# Package_Sockets.net
KiCad netlist of a schematic drawn in Altium Designer
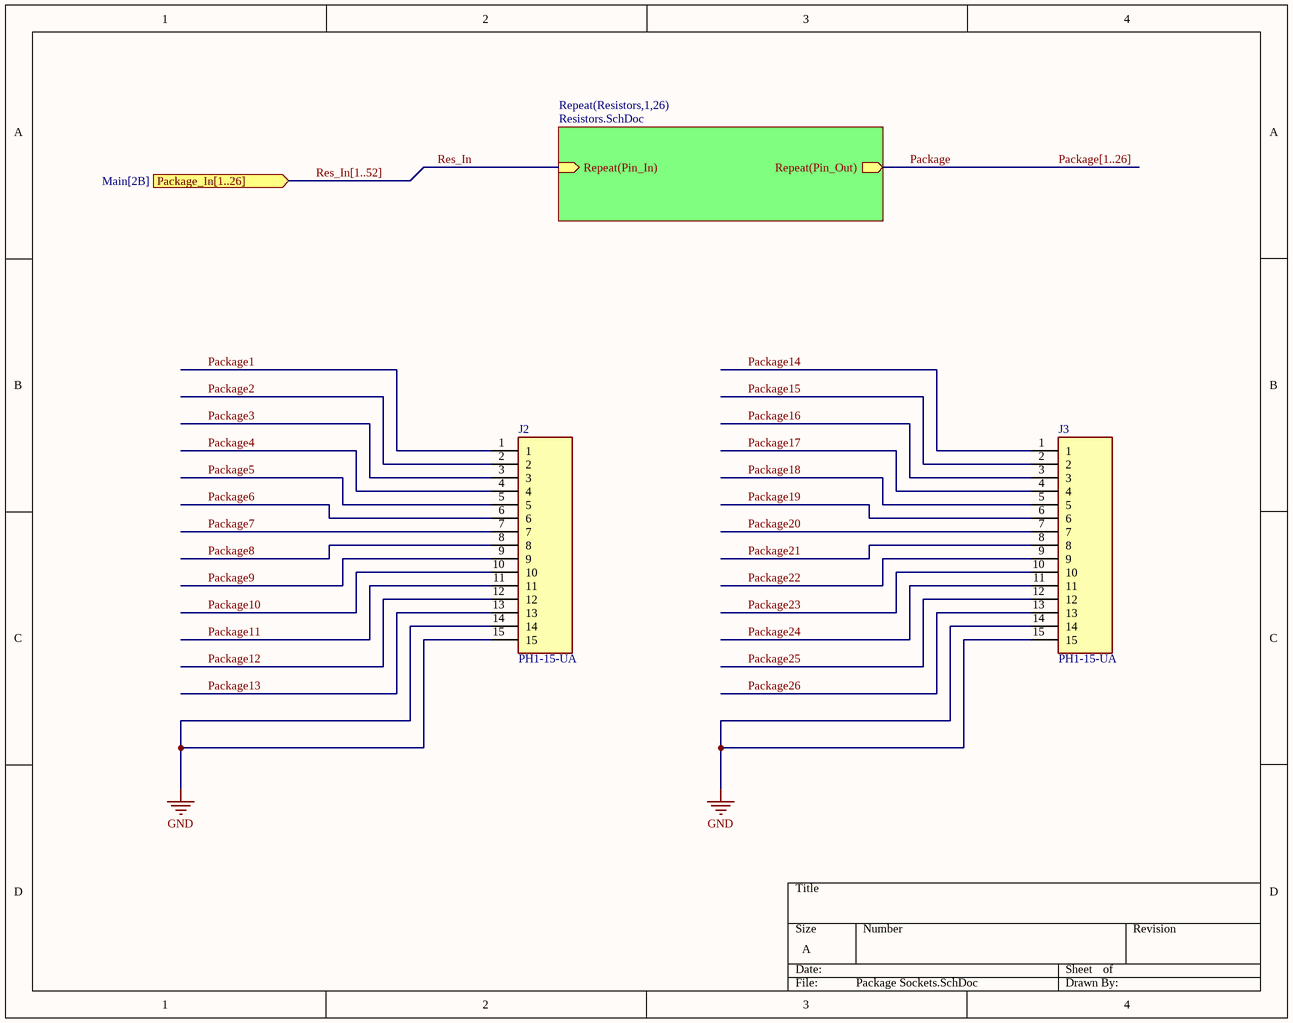
[diagram p0: Package Sockets.SchDoc]

(export (version "E")
  (design (tool "Eeschema 10.0.6"))
  (components
    (comp (ref "J2")
      (value "PH1-15-UA")
      (footprint "Packaging:HDRV15W64P0X254_1X15_3810X249X886P")
      (description "Connector")
      (fields (field (name "MOUSER PART NUMBER") "737-PH1-15-UA"))
      (libsource (lib "*") (part "PH1-15-UA"))
    )
    (comp (ref "J3")
      (value "PH1-15-UA")
      (footprint "Packaging:HDRV15W64P0X254_1X15_3810X249X886P")
      (description "Connector")
      (fields (field (name "MOUSER PART NUMBER") "737-PH1-15-UA"))
      (libsource (lib "*") (part "PH1-15-UA"))
    )
  )
  (nets
    (net (code "54") (name "/Package1") (class "Default")
      (node (ref "J2") (pin "1") (pinfunction "1_1") (pintype "passive"))
    )
    (net (code "55") (name "/Package2") (class "Default")
      (node (ref "J2") (pin "2") (pinfunction "2_2") (pintype "passive"))
    )
    (net (code "56") (name "/Package3") (class "Default")
      (node (ref "J2") (pin "3") (pinfunction "3_3") (pintype "passive"))
    )
    (net (code "57") (name "/Package4") (class "Default")
      (node (ref "J2") (pin "4") (pinfunction "4_4") (pintype "passive"))
    )
    (net (code "58") (name "/Package5") (class "Default")
      (node (ref "J2") (pin "5") (pinfunction "5_5") (pintype "passive"))
    )
    (net (code "59") (name "/Package6") (class "Default")
      (node (ref "J2") (pin "6") (pinfunction "6_6") (pintype "passive"))
    )
    (net (code "60") (name "/Package7") (class "Default")
      (node (ref "J2") (pin "7") (pinfunction "7_7") (pintype "passive"))
    )
    (net (code "61") (name "/Package8") (class "Default")
      (node (ref "J2") (pin "8") (pinfunction "8_8") (pintype "passive"))
    )
    (net (code "62") (name "/Package9") (class "Default")
      (node (ref "J2") (pin "9") (pinfunction "9_9") (pintype "passive"))
    )
    (net (code "63") (name "/Package10") (class "Default")
      (node (ref "J2") (pin "10") (pinfunction "10_10") (pintype "passive"))
    )
    (net (code "64") (name "/Package11") (class "Default")
      (node (ref "J2") (pin "11") (pinfunction "11_11") (pintype "passive"))
    )
    (net (code "65") (name "/Package12") (class "Default")
      (node (ref "J2") (pin "12") (pinfunction "12_12") (pintype "passive"))
    )
    (net (code "66") (name "/Package13") (class "Default")
      (node (ref "J2") (pin "13") (pinfunction "13_13") (pintype "passive"))
    )
    (net (code "67") (name "/Package14") (class "Default")
      (node (ref "J3") (pin "1") (pinfunction "1_1") (pintype "passive"))
    )
    (net (code "68") (name "/Package15") (class "Default")
      (node (ref "J3") (pin "2") (pinfunction "2_2") (pintype "passive"))
    )
    (net (code "69") (name "/Package16") (class "Default")
      (node (ref "J3") (pin "3") (pinfunction "3_3") (pintype "passive"))
    )
    (net (code "70") (name "/Package17") (class "Default")
      (node (ref "J3") (pin "4") (pinfunction "4_4") (pintype "passive"))
    )
    (net (code "71") (name "/Package18") (class "Default")
      (node (ref "J3") (pin "5") (pinfunction "5_5") (pintype "passive"))
    )
    (net (code "72") (name "/Package19") (class "Default")
      (node (ref "J3") (pin "6") (pinfunction "6_6") (pintype "passive"))
    )
    (net (code "73") (name "/Package20") (class "Default")
      (node (ref "J3") (pin "7") (pinfunction "7_7") (pintype "passive"))
    )
    (net (code "74") (name "/Package21") (class "Default")
      (node (ref "J3") (pin "8") (pinfunction "8_8") (pintype "passive"))
    )
    (net (code "75") (name "/Package22") (class "Default")
      (node (ref "J3") (pin "9") (pinfunction "9_9") (pintype "passive"))
    )
    (net (code "76") (name "/Package23") (class "Default")
      (node (ref "J3") (pin "10") (pinfunction "10_10") (pintype "passive"))
    )
    (net (code "77") (name "/Package24") (class "Default")
      (node (ref "J3") (pin "11") (pinfunction "11_11") (pintype "passive"))
    )
    (net (code "78") (name "/Package25") (class "Default")
      (node (ref "J3") (pin "12") (pinfunction "12_12") (pintype "passive"))
    )
    (net (code "79") (name "/Package26") (class "Default")
      (node (ref "J3") (pin "13") (pinfunction "13_13") (pintype "passive"))
    )
    (net (code "83") (name "GND") (class "Default")
      (node (ref "J2") (pin "14") (pinfunction "14_14") (pintype "passive"))
      (node (ref "J2") (pin "15") (pinfunction "15_15") (pintype "passive"))
      (node (ref "J3") (pin "14") (pinfunction "14_14") (pintype "passive"))
      (node (ref "J3") (pin "15") (pinfunction "15_15") (pintype "passive"))
    )
  )
)
